# UBW32_MX460_v262.net
KiCad netlist of a schematic drawn in Altium Designer
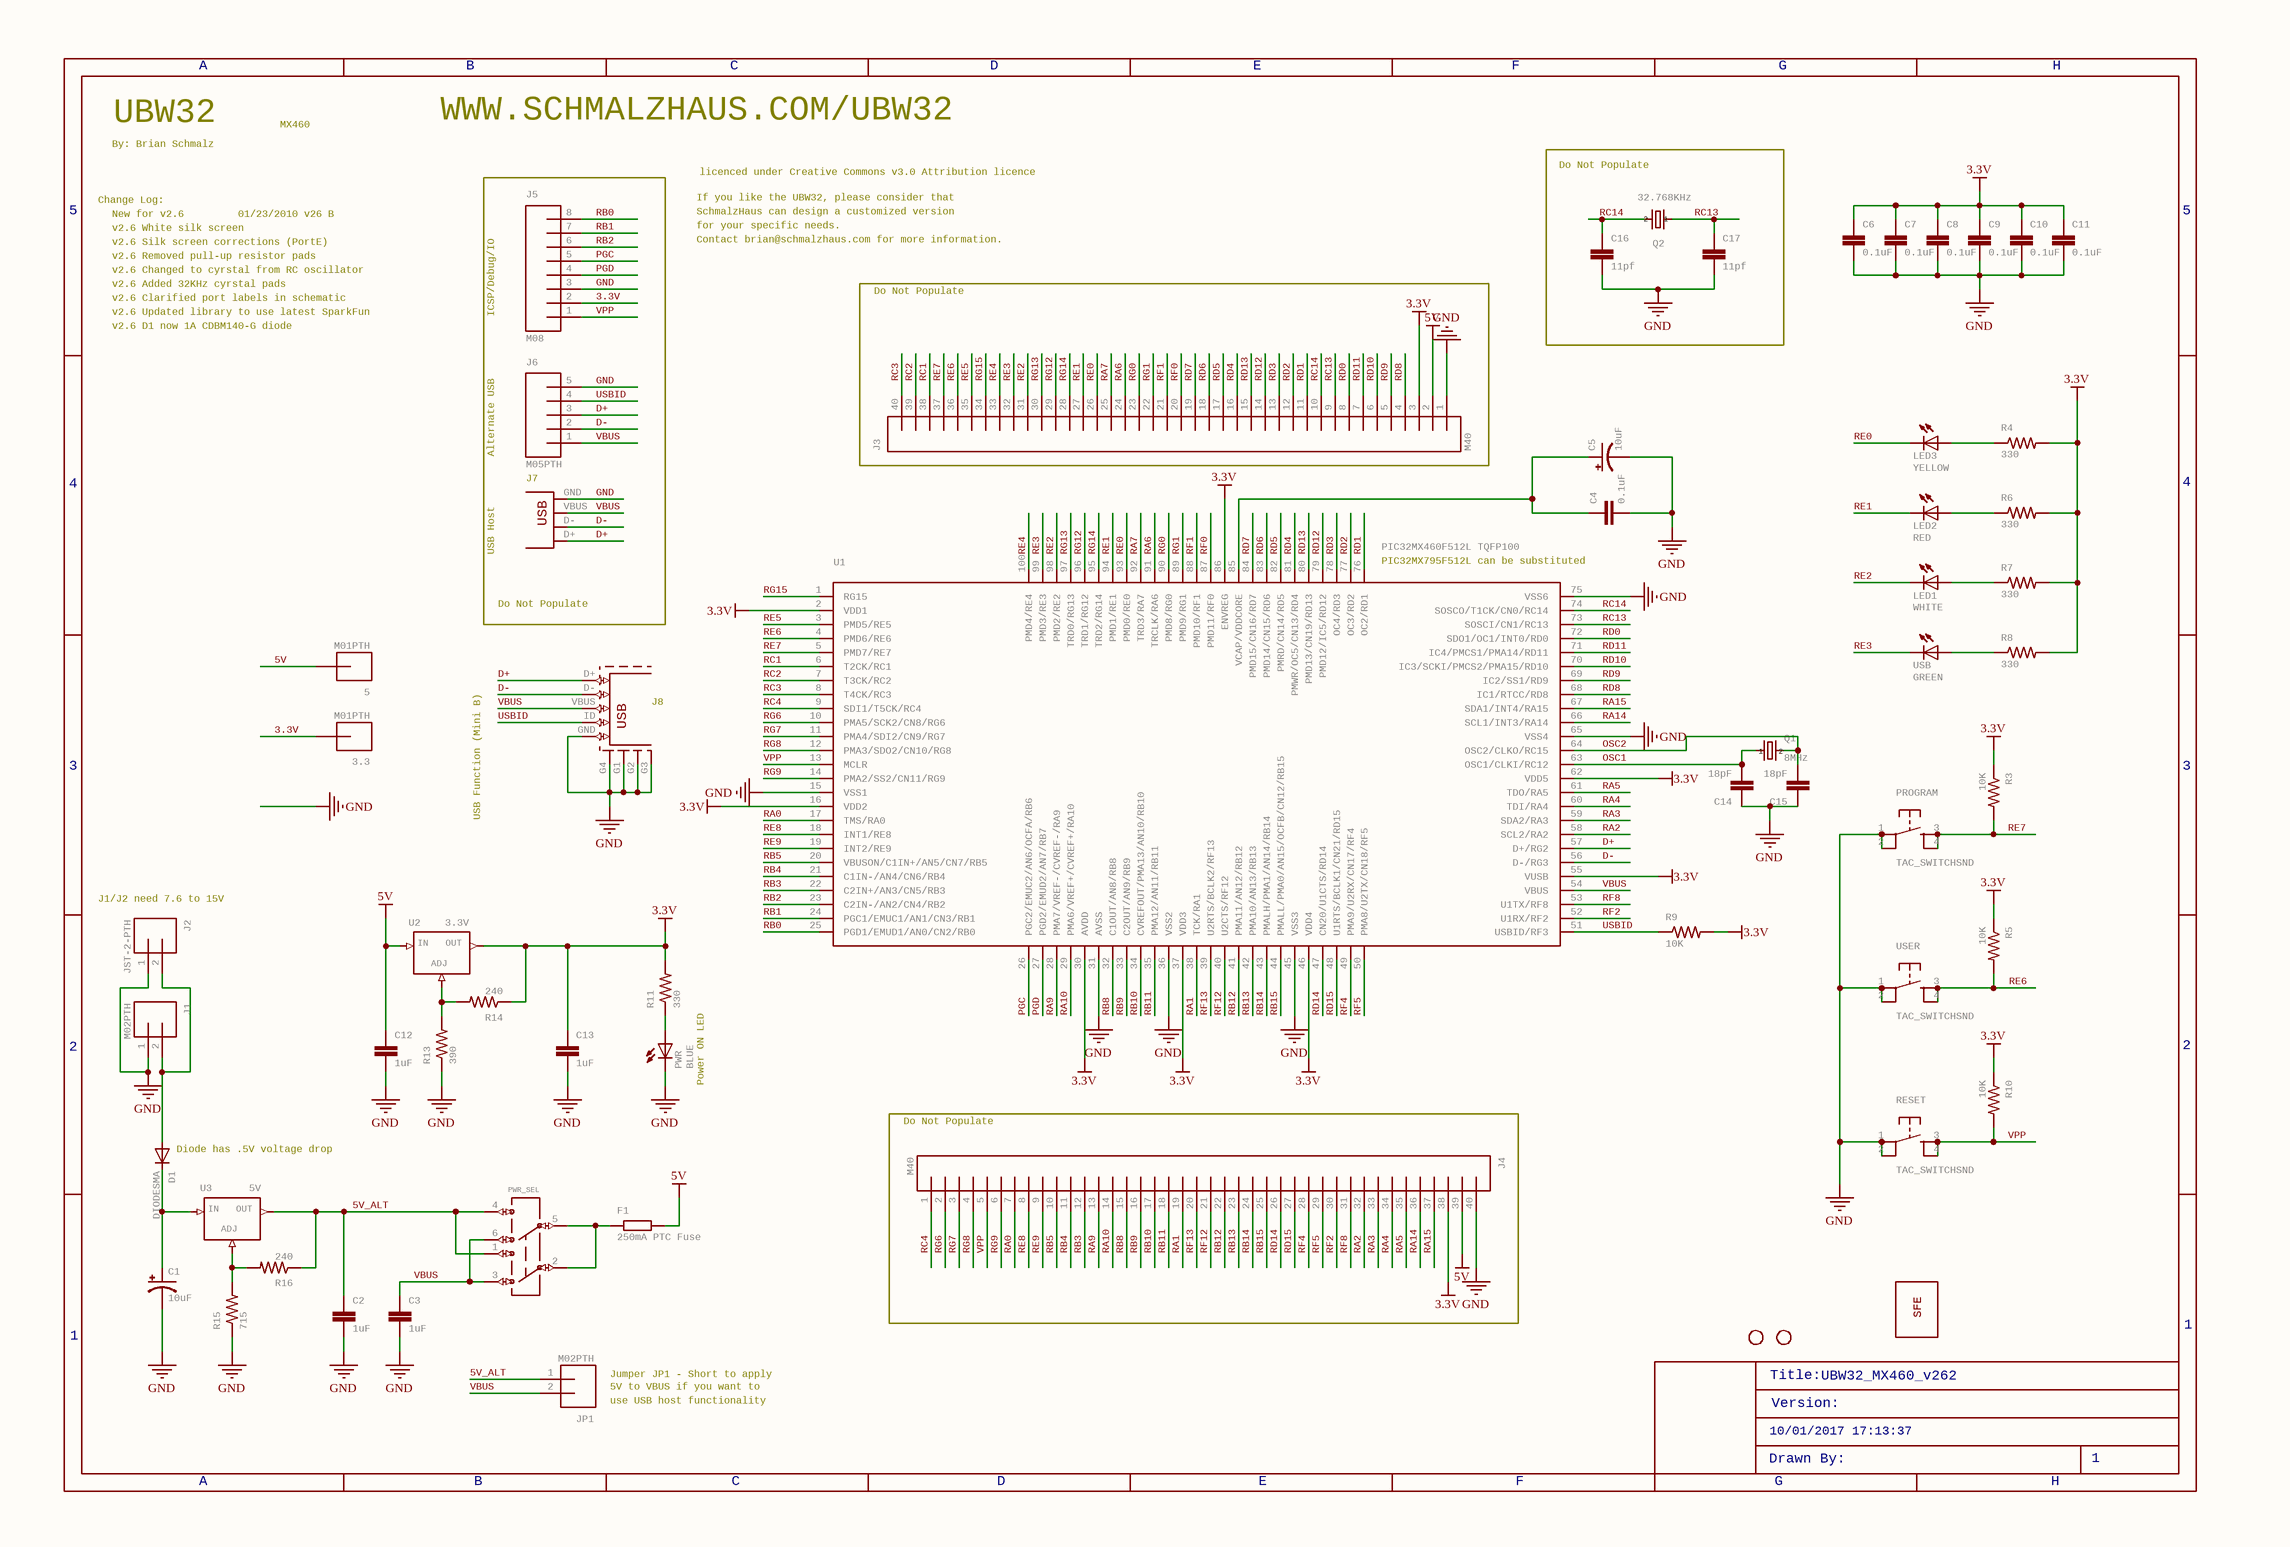
[diagram p0: UBW32_MX460_v262.SchDoc]

(export (version "E")
  (design (tool "Eeschema 10.0.6"))
  (components
    (comp (ref "3.3")
      (value "M01PTH")
      (footprint "1X01")
      (libsource (lib "SparkFun-12-01-09") (part "M01PTH"))
    )
    (comp (ref "5") (value "M01PTH") (footprint "1X01") (libsource (lib "SparkFun-12-01-09") (part "M01PTH")))
    (comp (ref "C1") (value "10uF") (footprint "EIA3528") (libsource (lib "") (part "CAP_POL3528_1")))
    (comp (ref "C2")
      (value "1uF")
      (footprint "0402-CAP")
      (description "CapacitorStandard 0603 ceramic capacitor, and 0.1\" leaded capacitor.")
      (libsource (lib "SparkFun") (part "CAP0402-CAP"))
    )
    (comp (ref "C3")
      (value "1uF")
      (footprint "0402-CAP")
      (description "CapacitorStandard 0603 ceramic capacitor, and 0.1\" leaded capacitor.")
      (libsource (lib "SparkFun") (part "CAP0402-CAP"))
    )
    (comp (ref "C4")
      (value "0.1uF")
      (footprint "0402-CAP")
      (description "CapacitorStandard 0603 ceramic capacitor, and 0.1\" leaded capacitor.")
      (libsource (lib "") (part "CAP0402-CAP_2"))
    )
    (comp (ref "C5")
      (value "10uF")
      (footprint "EIA3528")
      (libsource (lib "SparkFun02-20-08") (part "CAP_POL3528"))
    )
    (comp (ref "C6")
      (value "0.1uF")
      (footprint "0402-CAP")
      (description "CapacitorStandard 0603 ceramic capacitor, and 0.1\" leaded capacitor.")
      (libsource (lib "SparkFun") (part "CAP0402-CAP"))
    )
    (comp (ref "C7")
      (value "0.1uF")
      (footprint "0402-CAP")
      (description "CapacitorStandard 0603 ceramic capacitor, and 0.1\" leaded capacitor.")
      (libsource (lib "SparkFun") (part "CAP0402-CAP"))
    )
    (comp (ref "C8")
      (value "0.1uF")
      (footprint "0402-CAP")
      (description "CapacitorStandard 0603 ceramic capacitor, and 0.1\" leaded capacitor.")
      (libsource (lib "SparkFun") (part "CAP0402-CAP"))
    )
    (comp (ref "C9")
      (value "0.1uF")
      (footprint "0402-CAP")
      (description "CapacitorStandard 0603 ceramic capacitor, and 0.1\" leaded capacitor.")
      (libsource (lib "SparkFun") (part "CAP0402-CAP"))
    )
    (comp (ref "C10")
      (value "0.1uF")
      (footprint "C0402")
      (description "CapacitorStandard 0603 ceramic capacitor, and 0.1\" leaded capacitor.")
      (libsource (lib "SparkFun02-20-08") (part "CAP0402"))
    )
    (comp (ref "C11")
      (value "0.1uF")
      (footprint "0402-CAP")
      (description "CapacitorStandard 0603 ceramic capacitor, and 0.1\" leaded capacitor.")
      (libsource (lib "SparkFun") (part "CAP0402-CAP"))
    )
    (comp (ref "C12")
      (value "1uF")
      (footprint "C0402")
      (description "CapacitorStandard 0603 ceramic capacitor, and 0.1\" leaded capacitor.")
      (libsource (lib "SparkFun02-20-08") (part "CAP0402"))
    )
    (comp (ref "C13")
      (value "1uF")
      (footprint "C0402")
      (description "CapacitorStandard 0603 ceramic capacitor, and 0.1\" leaded capacitor.")
      (libsource (lib "SparkFun02-20-08") (part "CAP0402"))
    )
    (comp (ref "C14")
      (value "18pF")
      (footprint "0402-CAP")
      (description "CapacitorStandard 0603 ceramic capacitor, and 0.1\" leaded capacitor.")
      (libsource (lib "") (part "CAP0402-CAP_1"))
    )
    (comp (ref "C15")
      (value "18pF")
      (footprint "0402-CAP")
      (description "CapacitorStandard 0603 ceramic capacitor, and 0.1\" leaded capacitor.")
      (libsource (lib "") (part "CAP0402-CAP_1"))
    )
    (comp (ref "C16")
      (value "11pf")
      (footprint "0402-CAP")
      (description "CapacitorStandard 0603 ceramic capacitor, and 0.1\" leaded capacitor.")
      (libsource (lib "SparkFun") (part "CAP0402-CAP"))
    )
    (comp (ref "C17")
      (value "11pf")
      (footprint "0402-CAP")
      (description "CapacitorStandard 0603 ceramic capacitor, and 0.1\" leaded capacitor.")
      (libsource (lib "SparkFun") (part "CAP0402-CAP"))
    )
    (comp (ref "D1")
      (value "DIODESMA")
      (footprint "SMA-DIODE")
      (libsource (lib "SparkFun-12-01-09") (part "DIODESMA"))
    )
    (comp (ref "F1")
      (value "250mA PTC Fuse")
      (footprint "R1206")
      (description "RESISTOR, European symbol")
      (libsource (lib "resistor") (part "R-EU_R1206"))
    )
    (comp (ref "J1")
      (value "M02PTH")
      (footprint "1X02")
      (libsource (lib "SparkFun-12-01-09") (part "M02PTH"))
    )
    (comp (ref "J2")
      (value "JST-2-PTH")
      (footprint "S2B-PH")
      (libsource (lib "SparkFun") (part "M02-JST-2MM-SMT"))
    )
    (comp (ref "J3") (value "M40") (footprint "1X40") (libsource (lib "SchmalzHaus") (part "M40")))
    (comp (ref "J4") (value "M40") (footprint "1X40") (libsource (lib "SchmalzHaus") (part "M40")))
    (comp (ref "J5") (value "M08") (footprint "1X08") (libsource (lib "SchmalzHaus") (part "M08")))
    (comp (ref "J6")
      (value "M05PTH")
      (footprint "1X05")
      (libsource (lib "SparkFun-12-01-09") (part "M05PTH"))
    )
    (comp (ref "J7")
      (value "USB-A-S")
      (footprint "USB-A-S")
      (fields (field (name "USB") "USB"))
      (libsource (lib "SparkFun02-20-08") (part "USB-A-S"))
    )
    (comp (ref "J8")
      (value "~")
      (footprint "USB-MINIB")
      (fields (field (name "USB") "USB"))
      (libsource (lib "SparkFun02-20-08") (part "USB_5PIN"))
    )
    (comp (ref "JP1")
      (value "M02PTH")
      (footprint "1X02")
      (libsource (lib "SparkFun-12-01-09") (part "M02PTH"))
    )
    (comp (ref "LED1") (value "WHITE") (footprint "LED-0603") (libsource (lib "SparkFun") (part "LED0603")))
    (comp (ref "LED2") (value "RED") (footprint "LED-0603") (libsource (lib "SparkFun") (part "LED0603")))
    (comp (ref "LED3") (value "YELLOW") (footprint "LED-0603") (libsource (lib "SparkFun") (part "LED0603")))
    (comp (ref "PROGRAM")
      (value "TAC_SWITCHSND")
      (footprint "TACTILE_SWITCH_SMD")
      (libsource (lib "SparkFun02-20-08") (part "TAC_SWITCHSND"))
    )
    (comp (ref "PWR") (value "BLUE") (footprint "LED-0603") (libsource (lib "SparkFun") (part "LED0603")))
    (comp (ref "PWR_SEL")
      (value "AYZ0202")
      (footprint "AYZ0202")
      (libsource (lib "SparkFun02-20-08") (part "AYZ0202"))
    )
    (comp (ref "Q1")
      (value "8MHz")
      (footprint "CRYSTAL-SMD-5X3")
      (description "CrystalsVarious standard crystals. Proven footprints. Spark Fun Electronics SKU : COM-00534")
      (fields (field (name "1") "1") (field (name "2") "2"))
      (libsource (lib "SparkFun11_03_09") (part "CRYSTAL5X3"))
    )
    (comp (ref "Q2")
      (value "32.768KHz")
      (footprint "CRYSTAL-32KHZ-SMD")
      (description "CrystalsVarious standard crystals. Proven footprints. Spark Fun Electronics SKU : COM-00534")
      (fields (field (name "1") "1") (field (name "2") "2"))
      (libsource (lib "SchmalzHaus") (part "CRYSTAL32-SMD"))
    )
    (comp (ref "R3")
      (value "10K")
      (footprint "0402-RES")
      (libsource (lib "SparkFun") (part "RESISTOR0402-RES"))
    )
    (comp (ref "R4")
      (value "330")
      (footprint "0402-RES")
      (libsource (lib "SparkFun") (part "RESISTOR0402-RES"))
    )
    (comp (ref "R5")
      (value "10K")
      (footprint "0402-RES")
      (libsource (lib "SparkFun") (part "RESISTOR0402-RES"))
    )
    (comp (ref "R6")
      (value "330")
      (footprint "0402-RES")
      (libsource (lib "SparkFun") (part "RESISTOR0402-RES"))
    )
    (comp (ref "R7")
      (value "330")
      (footprint "0402-RES")
      (libsource (lib "SparkFun") (part "RESISTOR0402-RES"))
    )
    (comp (ref "R8")
      (value "330")
      (footprint "0402-RES")
      (libsource (lib "SparkFun") (part "RESISTOR0402-RES"))
    )
    (comp (ref "R9")
      (value "10K")
      (footprint "0402-RES")
      (libsource (lib "SparkFun") (part "RESISTOR0402-RES"))
    )
    (comp (ref "R10")
      (value "10K")
      (footprint "0402-RES")
      (libsource (lib "SparkFun") (part "RESISTOR0402-RES"))
    )
    (comp (ref "R11")
      (value "330")
      (footprint "0402-RES")
      (libsource (lib "SparkFun") (part "RESISTOR0402-RES"))
    )
    (comp (ref "R13")
      (value "390")
      (footprint "0402-RES")
      (libsource (lib "SparkFun") (part "RESISTOR0402-RES"))
    )
    (comp (ref "R14")
      (value "240")
      (footprint "0402-RES")
      (libsource (lib "SparkFun") (part "RESISTOR0402-RES"))
    )
    (comp (ref "R15")
      (value "715")
      (footprint "0402-RES")
      (libsource (lib "SparkFun") (part "RESISTOR0402-RES"))
    )
    (comp (ref "R16")
      (value "240")
      (footprint "0402-RES")
      (libsource (lib "SparkFun") (part "RESISTOR0402-RES"))
    )
    (comp (ref "RESET")
      (value "TAC_SWITCHSND")
      (footprint "TACTILE_SWITCH_SMD")
      (libsource (lib "SparkFun02-20-08") (part "TAC_SWITCHSND"))
    )
    (comp (ref "U$4")
      (value "LOGO-SFENEW")
      (footprint "SFE-NEW-WEBLOGO")
      (description "Spark Fun Electronics PCB LogoThis is the standard Spark Fun Electronics PCB logo.")
      (fields (field (name "SFE") "SFE"))
      (libsource (lib "SparkFun02-20-08") (part "LOGO-SFENEW"))
    )
    (comp (ref "U$6")
      (value "STAND-OFF")
      (footprint "STAND-OFF")
      (libsource (lib "SparkFun02-20-08") (part "STAND-OFF"))
    )
    (comp (ref "U$7")
      (value "STAND-OFF")
      (footprint "STAND-OFF")
      (libsource (lib "SparkFun02-20-08") (part "STAND-OFF"))
    )
    (comp (ref "U1")
      (value "PIC32MX460F512L TQFP100")
      (footprint "TQFP100")
      (libsource (lib "SchmalzHaus") (part "PIC32MX4XXLTQFP100"))
    )
    (comp (ref "U2")
      (value "3.3V")
      (footprint "SOT223")
      (fields (field (name "ADJ") "ADJ") (field (name "IN") "IN") (field (name "OUT") "OUT"))
      (libsource (lib "SparkFun") (part "V_REG_317SMD"))
    )
    (comp (ref "U3")
      (value "5V")
      (footprint "SOT223")
      (fields (field (name "ADJ") "ADJ") (field (name "IN") "IN") (field (name "OUT") "OUT"))
      (libsource (lib "SparkFun") (part "V_REG_317SMD"))
    )
    (comp (ref "USB") (value "GREEN") (footprint "LED-0603") (libsource (lib "SparkFun") (part "LED0603")))
    (comp (ref "USER")
      (value "TAC_SWITCHSND")
      (footprint "TACTILE_SWITCH_SMD")
      (libsource (lib "SparkFun02-20-08") (part "TAC_SWITCHSND"))
    )
  )
  (nets
    (net (code "1") (name "/5V_ALT") (class "Default")
      (node (ref "C2") (pin "1") (pinfunction "1_1") (pintype "passive"))
      (node (ref "JP1") (pin "1") (pinfunction "1_1") (pintype "passive"))
      (node (ref "PWR_SEL") (pin "1") (pinfunction "3_1") (pintype "bidirectional"))
      (node (ref "PWR_SEL") (pin "4") (pinfunction "6_4") (pintype "bidirectional"))
      (node (ref "R16") (pin "1") (pinfunction "1_1") (pintype "passive"))
      (node (ref "U3") (pin "2") (pinfunction "OUT_2") (pintype "output"))
    )
    (net (code "2") (name "/D+") (class "Default")
      (node (ref "J6") (pin "3") (pinfunction "3_3") (pintype "passive"))
      (node (ref "J7") (pin "D+") (pinfunction "D+_D+") (pintype "bidirectional"))
      (node (ref "J8") (pin "D+") (pinfunction "D+_D+") (pintype "bidirectional"))
      (node (ref "U1") (pin "57") (pinfunction "D+/RG2_57") (pintype "bidirectional"))
    )
    (net (code "3") (name "/D-") (class "Default")
      (node (ref "J6") (pin "2") (pinfunction "2_2") (pintype "passive"))
      (node (ref "J7") (pin "D-") (pinfunction "D-_D-") (pintype "bidirectional"))
      (node (ref "J8") (pin "D-") (pinfunction "D-_D-") (pintype "bidirectional"))
      (node (ref "U1") (pin "56") (pinfunction "D-/RG3_56") (pintype "bidirectional"))
    )
    (net (code "4") (name "/OSC1") (class "Default")
      (node (ref "C14") (pin "2") (pinfunction "2_2") (pintype "passive"))
      (node (ref "Q1") (pin "1") (pinfunction "1_1") (pintype "passive"))
      (node (ref "U1") (pin "63") (pinfunction "OSC1/CLKI/RC12_63") (pintype "bidirectional"))
    )
    (net (code "5") (name "/OSC2") (class "Default")
      (node (ref "C15") (pin "2") (pinfunction "2_2") (pintype "passive"))
      (node (ref "Q1") (pin "3") (pinfunction "2_3") (pintype "passive"))
      (node (ref "U1") (pin "64") (pinfunction "OSC2/CLKO/RC15_64") (pintype "bidirectional"))
    )
    (net (code "6") (name "/PGC") (class "Default")
      (node (ref "J5") (pin "5") (pinfunction "5_5") (pintype "passive"))
      (node (ref "U1") (pin "26") (pinfunction "PGC2/EMUC2/AN6/OCFA/RB6_26") (pintype "bidirectional"))
    )
    (net (code "7") (name "/PGD") (class "Default")
      (node (ref "J5") (pin "4") (pinfunction "4_4") (pintype "passive"))
      (node (ref "U1") (pin "27") (pinfunction "PGD2/EMUD2/AN7/RB7_27") (pintype "bidirectional"))
    )
    (net (code "8") (name "/RA0") (class "Default")
      (node (ref "J4") (pin "7") (pinfunction "7_7") (pintype "passive"))
      (node (ref "U1") (pin "17") (pinfunction "TMS/RA0_17") (pintype "bidirectional"))
    )
    (net (code "9") (name "/RA1") (class "Default")
      (node (ref "J4") (pin "19") (pinfunction "19_19") (pintype "passive"))
      (node (ref "U1") (pin "38") (pinfunction "TCK/RA1_38") (pintype "bidirectional"))
    )
    (net (code "10") (name "/RA2") (class "Default")
      (node (ref "J4") (pin "32") (pinfunction "32_32") (pintype "passive"))
      (node (ref "U1") (pin "58") (pinfunction "SCL2/RA2_58") (pintype "bidirectional"))
    )
    (net (code "11") (name "/RA3") (class "Default")
      (node (ref "J4") (pin "33") (pinfunction "33_33") (pintype "passive"))
      (node (ref "U1") (pin "59") (pinfunction "SDA2/RA3_59") (pintype "bidirectional"))
    )
    (net (code "12") (name "/RA4") (class "Default")
      (node (ref "J4") (pin "34") (pinfunction "34_34") (pintype "passive"))
      (node (ref "U1") (pin "60") (pinfunction "TDI/RA4_60") (pintype "bidirectional"))
    )
    (net (code "13") (name "/RA5") (class "Default")
      (node (ref "J4") (pin "35") (pinfunction "35_35") (pintype "passive"))
      (node (ref "U1") (pin "61") (pinfunction "TDO/RA5_61") (pintype "bidirectional"))
    )
    (net (code "14") (name "/RA6") (class "Default")
      (node (ref "J3") (pin "24") (pinfunction "24_24") (pintype "passive"))
      (node (ref "U1") (pin "91") (pinfunction "TRCLK/RA6_91") (pintype "bidirectional"))
    )
    (net (code "15") (name "/RA7") (class "Default")
      (node (ref "J3") (pin "25") (pinfunction "25_25") (pintype "passive"))
      (node (ref "U1") (pin "92") (pinfunction "TRD3/RA7_92") (pintype "bidirectional"))
    )
    (net (code "16") (name "/RA9") (class "Default")
      (node (ref "J4") (pin "13") (pinfunction "13_13") (pintype "passive"))
      (node (ref "U1") (pin "28") (pinfunction "PMA7/VREF-/CVREF-/RA9_28") (pintype "bidirectional"))
    )
    (net (code "17") (name "/RA10") (class "Default")
      (node (ref "J4") (pin "14") (pinfunction "14_14") (pintype "passive"))
      (node (ref "U1") (pin "29") (pinfunction "PMA6/VREF+/CVREF+/RA10_29") (pintype "bidirectional"))
    )
    (net (code "18") (name "/RA14") (class "Default")
      (node (ref "J4") (pin "36") (pinfunction "36_36") (pintype "passive"))
      (node (ref "U1") (pin "66") (pinfunction "SCL1/INT3/RA14_66") (pintype "bidirectional"))
    )
    (net (code "19") (name "/RA15") (class "Default")
      (node (ref "J4") (pin "37") (pinfunction "37_37") (pintype "passive"))
      (node (ref "U1") (pin "67") (pinfunction "SDA1/INT4/RA15_67") (pintype "bidirectional"))
    )
    (net (code "20") (name "/RB0") (class "Default")
      (node (ref "J5") (pin "8") (pinfunction "8_8") (pintype "passive"))
      (node (ref "U1") (pin "25") (pinfunction "PGD1/EMUD1/AN0/CN2/RB0_25") (pintype "bidirectional"))
    )
    (net (code "21") (name "/RB1") (class "Default")
      (node (ref "J5") (pin "7") (pinfunction "7_7") (pintype "passive"))
      (node (ref "U1") (pin "24") (pinfunction "PGC1/EMUC1/AN1/CN3/RB1_24") (pintype "bidirectional"))
    )
    (net (code "22") (name "/RB2") (class "Default")
      (node (ref "J5") (pin "6") (pinfunction "6_6") (pintype "passive"))
      (node (ref "U1") (pin "23") (pinfunction "C2IN-/AN2/CN4/RB2_23") (pintype "bidirectional"))
    )
    (net (code "23") (name "/RB3") (class "Default")
      (node (ref "J4") (pin "12") (pinfunction "12_12") (pintype "passive"))
      (node (ref "U1") (pin "22") (pinfunction "C2IN+/AN3/CN5/RB3_22") (pintype "bidirectional"))
    )
    (net (code "24") (name "/RB4") (class "Default")
      (node (ref "J4") (pin "11") (pinfunction "11_11") (pintype "passive"))
      (node (ref "U1") (pin "21") (pinfunction "C1IN-/AN4/CN6/RB4_21") (pintype "bidirectional"))
    )
    (net (code "25") (name "/RB5") (class "Default")
      (node (ref "J4") (pin "10") (pinfunction "10_10") (pintype "passive"))
      (node (ref "U1") (pin "20") (pinfunction "VBUSON/C1IN+/AN5/CN7/RB5_20") (pintype "bidirectional"))
    )
    (net (code "26") (name "/RB8") (class "Default")
      (node (ref "J4") (pin "15") (pinfunction "15_15") (pintype "passive"))
      (node (ref "U1") (pin "32") (pinfunction "C1OUT/AN8/RB8_32") (pintype "bidirectional"))
    )
    (net (code "27") (name "/RB9") (class "Default")
      (node (ref "J4") (pin "16") (pinfunction "16_16") (pintype "passive"))
      (node (ref "U1") (pin "33") (pinfunction "C2OUT/AN9/RB9_33") (pintype "bidirectional"))
    )
    (net (code "28") (name "/RB10") (class "Default")
      (node (ref "J4") (pin "17") (pinfunction "17_17") (pintype "passive"))
      (node (ref "U1") (pin "34") (pinfunction "CVREFOUT/PMA13/AN10/RB10_34") (pintype "bidirectional"))
    )
    (net (code "29") (name "/RB11") (class "Default")
      (node (ref "J4") (pin "18") (pinfunction "18_18") (pintype "passive"))
      (node (ref "U1") (pin "35") (pinfunction "PMA12/AN11/RB11_35") (pintype "bidirectional"))
    )
    (net (code "30") (name "/RB12") (class "Default")
      (node (ref "J4") (pin "22") (pinfunction "22_22") (pintype "passive"))
      (node (ref "U1") (pin "41") (pinfunction "PMA11/AN12/RB12_41") (pintype "bidirectional"))
    )
    (net (code "31") (name "/RB13") (class "Default")
      (node (ref "J4") (pin "23") (pinfunction "23_23") (pintype "passive"))
      (node (ref "U1") (pin "42") (pinfunction "PMA10/AN13/RB13_42") (pintype "bidirectional"))
    )
    (net (code "32") (name "/RB14") (class "Default")
      (node (ref "J4") (pin "24") (pinfunction "24_24") (pintype "passive"))
      (node (ref "U1") (pin "43") (pinfunction "PMALH/PMA1/AN14/RB14_43") (pintype "bidirectional"))
    )
    (net (code "33") (name "/RB15") (class "Default")
      (node (ref "J4") (pin "25") (pinfunction "25_25") (pintype "passive"))
      (node (ref "U1") (pin "44") (pinfunction "PMALL/PMA0/AN15/OCFB/CN12/RB15_44") (pintype "bidirectional"))
    )
    (net (code "34") (name "/RC1") (class "Default")
      (node (ref "J3") (pin "38") (pinfunction "38_38") (pintype "passive"))
      (node (ref "U1") (pin "6") (pinfunction "T2CK/RC1_6") (pintype "bidirectional"))
    )
    (net (code "35") (name "/RC2") (class "Default")
      (node (ref "J3") (pin "39") (pinfunction "39_39") (pintype "passive"))
      (node (ref "U1") (pin "7") (pinfunction "T3CK/RC2_7") (pintype "bidirectional"))
    )
    (net (code "36") (name "/RC3") (class "Default")
      (node (ref "J3") (pin "40") (pinfunction "40_40") (pintype "passive"))
      (node (ref "U1") (pin "8") (pinfunction "T4CK/RC3_8") (pintype "bidirectional"))
    )
    (net (code "37") (name "/RC4") (class "Default")
      (node (ref "J4") (pin "1") (pinfunction "1_1") (pintype "passive"))
      (node (ref "U1") (pin "9") (pinfunction "SDI1/T5CK/RC4_9") (pintype "bidirectional"))
    )
    (net (code "38") (name "/RC13") (class "Default")
      (node (ref "C17") (pin "1") (pinfunction "1_1") (pintype "passive"))
      (node (ref "J3") (pin "9") (pinfunction "9_9") (pintype "passive"))
      (node (ref "Q2") (pin "X1") (pinfunction "1_X1") (pintype "passive"))
      (node (ref "U1") (pin "73") (pinfunction "SOSCI/CN1/RC13_73") (pintype "bidirectional"))
    )
    (net (code "39") (name "/RC14") (class "Default")
      (node (ref "C16") (pin "1") (pinfunction "1_1") (pintype "passive"))
      (node (ref "J3") (pin "10") (pinfunction "10_10") (pintype "passive"))
      (node (ref "Q2") (pin "X2") (pinfunction "2_X2") (pintype "passive"))
      (node (ref "U1") (pin "74") (pinfunction "SOSCO/T1CK/CN0/RC14_74") (pintype "bidirectional"))
    )
    (net (code "40") (name "/RD0") (class "Default")
      (node (ref "J3") (pin "8") (pinfunction "8_8") (pintype "passive"))
      (node (ref "U1") (pin "72") (pinfunction "SDO1/OC1/INT0/RD0_72") (pintype "bidirectional"))
    )
    (net (code "41") (name "/RD1") (class "Default")
      (node (ref "J3") (pin "11") (pinfunction "11_11") (pintype "passive"))
      (node (ref "U1") (pin "76") (pinfunction "OC2/RD1_76") (pintype "bidirectional"))
    )
    (net (code "42") (name "/RD2") (class "Default")
      (node (ref "J3") (pin "12") (pinfunction "12_12") (pintype "passive"))
      (node (ref "U1") (pin "77") (pinfunction "OC3/RD2_77") (pintype "bidirectional"))
    )
    (net (code "43") (name "/RD3") (class "Default")
      (node (ref "J3") (pin "13") (pinfunction "13_13") (pintype "passive"))
      (node (ref "U1") (pin "78") (pinfunction "OC4/RD3_78") (pintype "bidirectional"))
    )
    (net (code "44") (name "/RD4") (class "Default")
      (node (ref "J3") (pin "16") (pinfunction "16_16") (pintype "passive"))
      (node (ref "U1") (pin "81") (pinfunction "PMWR/OC5/CN13/RD4_81") (pintype "bidirectional"))
    )
    (net (code "45") (name "/RD5") (class "Default")
      (node (ref "J3") (pin "17") (pinfunction "17_17") (pintype "passive"))
      (node (ref "U1") (pin "82") (pinfunction "PMRD/CN14/RD5_82") (pintype "bidirectional"))
    )
    (net (code "46") (name "/RD6") (class "Default")
      (node (ref "J3") (pin "18") (pinfunction "18_18") (pintype "passive"))
      (node (ref "U1") (pin "83") (pinfunction "PMD14/CN15/RD6_83") (pintype "bidirectional"))
    )
    (net (code "47") (name "/RD7") (class "Default")
      (node (ref "J3") (pin "19") (pinfunction "19_19") (pintype "passive"))
      (node (ref "U1") (pin "84") (pinfunction "PMD15/CN16/RD7_84") (pintype "bidirectional"))
    )
    (net (code "48") (name "/RD8") (class "Default")
      (node (ref "J3") (pin "4") (pinfunction "4_4") (pintype "passive"))
      (node (ref "U1") (pin "68") (pinfunction "IC1/RTCC/RD8_68") (pintype "bidirectional"))
    )
    (net (code "49") (name "/RD9") (class "Default")
      (node (ref "J3") (pin "5") (pinfunction "5_5") (pintype "passive"))
      (node (ref "U1") (pin "69") (pinfunction "IC2/SS1/RD9_69") (pintype "bidirectional"))
    )
    (net (code "50") (name "/RD10") (class "Default")
      (node (ref "J3") (pin "6") (pinfunction "6_6") (pintype "passive"))
      (node (ref "U1") (pin "70") (pinfunction "IC3/SCKI/PMCS2/PMA15/RD10_70") (pintype "bidirectional"))
    )
    (net (code "51") (name "/RD11") (class "Default")
      (node (ref "J3") (pin "7") (pinfunction "7_7") (pintype "passive"))
      (node (ref "U1") (pin "71") (pinfunction "IC4/PMCS1/PMA14/RD11_71") (pintype "bidirectional"))
    )
    (net (code "52") (name "/RD12") (class "Default")
      (node (ref "J3") (pin "14") (pinfunction "14_14") (pintype "passive"))
      (node (ref "U1") (pin "79") (pinfunction "PMD12/IC5/RD12_79") (pintype "bidirectional"))
    )
    (net (code "53") (name "/RD13") (class "Default")
      (node (ref "J3") (pin "15") (pinfunction "15_15") (pintype "passive"))
      (node (ref "U1") (pin "80") (pinfunction "PMD13/CN19/RD13_80") (pintype "bidirectional"))
    )
    (net (code "54") (name "/RD14") (class "Default")
      (node (ref "J4") (pin "26") (pinfunction "26_26") (pintype "passive"))
      (node (ref "U1") (pin "47") (pinfunction "CN20/U1CTS/RD14_47") (pintype "bidirectional"))
    )
    (net (code "55") (name "/RD15") (class "Default")
      (node (ref "J4") (pin "27") (pinfunction "27_27") (pintype "passive"))
      (node (ref "U1") (pin "48") (pinfunction "U1RTS/BCLK1/CN21/RD15_48") (pintype "bidirectional"))
    )
    (net (code "56") (name "/RE0") (class "Default")
      (node (ref "J3") (pin "26") (pinfunction "26_26") (pintype "passive"))
      (node (ref "LED3") (pin "C") (pinfunction "C_C") (pintype "passive"))
      (node (ref "U1") (pin "93") (pinfunction "PMD0/RE0_93") (pintype "bidirectional"))
    )
    (net (code "57") (name "/RE1") (class "Default")
      (node (ref "J3") (pin "27") (pinfunction "27_27") (pintype "passive"))
      (node (ref "LED2") (pin "C") (pinfunction "C_C") (pintype "passive"))
      (node (ref "U1") (pin "94") (pinfunction "PMD1/RE1_94") (pintype "bidirectional"))
    )
    (net (code "58") (name "/RE2") (class "Default")
      (node (ref "J3") (pin "31") (pinfunction "31_31") (pintype "passive"))
      (node (ref "LED1") (pin "C") (pinfunction "C_C") (pintype "passive"))
      (node (ref "U1") (pin "98") (pinfunction "PMD2/RE2_98") (pintype "bidirectional"))
    )
    (net (code "59") (name "/RE3") (class "Default")
      (node (ref "J3") (pin "32") (pinfunction "32_32") (pintype "passive"))
      (node (ref "U1") (pin "99") (pinfunction "PMD3/RE3_99") (pintype "bidirectional"))
      (node (ref "USB") (pin "C") (pinfunction "C_C") (pintype "passive"))
    )
    (net (code "60") (name "/RE4") (class "Default")
      (node (ref "J3") (pin "33") (pinfunction "33_33") (pintype "passive"))
      (node (ref "U1") (pin "100") (pinfunction "PMD4/RE4_100") (pintype "bidirectional"))
    )
    (net (code "61") (name "/RE5") (class "Default")
      (node (ref "J3") (pin "35") (pinfunction "35_35") (pintype "passive"))
      (node (ref "U1") (pin "3") (pinfunction "PMD5/RE5_3") (pintype "bidirectional"))
    )
    (net (code "62") (name "/RE6") (class "Default")
      (node (ref "J3") (pin "36") (pinfunction "36_36") (pintype "passive"))
      (node (ref "R5") (pin "2") (pinfunction "2_2") (pintype "passive"))
      (node (ref "U1") (pin "4") (pinfunction "PMD6/RE6_4") (pintype "bidirectional"))
      (node (ref "USER") (pin "3") (pinfunction "3_3") (pintype "passive"))
      (node (ref "USER") (pin "4") (pinfunction "4_4") (pintype "passive"))
    )
    (net (code "63") (name "/RE7") (class "Default")
      (node (ref "J3") (pin "37") (pinfunction "37_37") (pintype "passive"))
      (node (ref "PROGRAM") (pin "3") (pinfunction "3_3") (pintype "passive"))
      (node (ref "PROGRAM") (pin "4") (pinfunction "4_4") (pintype "passive"))
      (node (ref "R3") (pin "2") (pinfunction "2_2") (pintype "passive"))
      (node (ref "U1") (pin "5") (pinfunction "PMD7/RE7_5") (pintype "bidirectional"))
    )
    (net (code "64") (name "/RE8") (class "Default")
      (node (ref "J4") (pin "8") (pinfunction "8_8") (pintype "passive"))
      (node (ref "U1") (pin "18") (pinfunction "INT1/RE8_18") (pintype "bidirectional"))
    )
    (net (code "65") (name "/RE9") (class "Default")
      (node (ref "J4") (pin "9") (pinfunction "9_9") (pintype "passive"))
      (node (ref "U1") (pin "19") (pinfunction "INT2/RE9_19") (pintype "bidirectional"))
    )
    (net (code "66") (name "/RF0") (class "Default")
      (node (ref "J3") (pin "20") (pinfunction "20_20") (pintype "passive"))
      (node (ref "U1") (pin "87") (pinfunction "PMD11/RF0_87") (pintype "bidirectional"))
    )
    (net (code "67") (name "/RF1") (class "Default")
      (node (ref "J3") (pin "21") (pinfunction "21_21") (pintype "passive"))
      (node (ref "U1") (pin "88") (pinfunction "PMD10/RF1_88") (pintype "bidirectional"))
    )
    (net (code "68") (name "/RF2") (class "Default")
      (node (ref "J4") (pin "30") (pinfunction "30_30") (pintype "passive"))
      (node (ref "U1") (pin "52") (pinfunction "U1RX/RF2_52") (pintype "bidirectional"))
    )
    (net (code "69") (name "/RF4") (class "Default")
      (node (ref "J4") (pin "28") (pinfunction "28_28") (pintype "passive"))
      (node (ref "U1") (pin "49") (pinfunction "PMA9/U2RX/CN17/RF4_49") (pintype "bidirectional"))
    )
    (net (code "70") (name "/RF5") (class "Default")
      (node (ref "J4") (pin "29") (pinfunction "29_29") (pintype "passive"))
      (node (ref "U1") (pin "50") (pinfunction "PMA8/U2TX/CN18/RF5_50") (pintype "bidirectional"))
    )
    (net (code "71") (name "/RF8") (class "Default")
      (node (ref "J4") (pin "31") (pinfunction "31_31") (pintype "passive"))
      (node (ref "U1") (pin "53") (pinfunction "U1TX/RF8_53") (pintype "bidirectional"))
    )
    (net (code "72") (name "/RF12") (class "Default")
      (node (ref "J4") (pin "21") (pinfunction "21_21") (pintype "passive"))
      (node (ref "U1") (pin "40") (pinfunction "U2CTS/RF12_40") (pintype "bidirectional"))
    )
    (net (code "73") (name "/RF13") (class "Default")
      (node (ref "J4") (pin "20") (pinfunction "20_20") (pintype "passive"))
      (node (ref "U1") (pin "39") (pinfunction "U2RTS/BCLK2/RF13_39") (pintype "bidirectional"))
    )
    (net (code "74") (name "/RG0") (class "Default")
      (node (ref "J3") (pin "23") (pinfunction "23_23") (pintype "passive"))
      (node (ref "U1") (pin "90") (pinfunction "PMD8/RG0_90") (pintype "bidirectional"))
    )
    (net (code "75") (name "/RG1") (class "Default")
      (node (ref "J3") (pin "22") (pinfunction "22_22") (pintype "passive"))
      (node (ref "U1") (pin "89") (pinfunction "PMD9/RG1_89") (pintype "bidirectional"))
    )
    (net (code "76") (name "/RG6") (class "Default")
      (node (ref "J4") (pin "2") (pinfunction "2_2") (pintype "passive"))
      (node (ref "U1") (pin "10") (pinfunction "PMA5/SCK2/CN8/RG6_10") (pintype "bidirectional"))
    )
    (net (code "77") (name "/RG7") (class "Default")
      (node (ref "J4") (pin "3") (pinfunction "3_3") (pintype "passive"))
      (node (ref "U1") (pin "11") (pinfunction "PMA4/SDI2/CN9/RG7_11") (pintype "bidirectional"))
    )
    (net (code "78") (name "/RG8") (class "Default")
      (node (ref "J4") (pin "4") (pinfunction "4_4") (pintype "passive"))
      (node (ref "U1") (pin "12") (pinfunction "PMA3/SDO2/CN10/RG8_12") (pintype "bidirectional"))
    )
    (net (code "79") (name "/RG9") (class "Default")
      (node (ref "J4") (pin "6") (pinfunction "6_6") (pintype "passive"))
      (node (ref "U1") (pin "14") (pinfunction "PMA2/SS2/CN11/RG9_14") (pintype "bidirectional"))
    )
    (net (code "80") (name "/RG12") (class "Default")
      (node (ref "J3") (pin "29") (pinfunction "29_29") (pintype "passive"))
      (node (ref "U1") (pin "96") (pinfunction "TRD1/RG12_96") (pintype "bidirectional"))
    )
    (net (code "81") (name "/RG13") (class "Default")
      (node (ref "J3") (pin "30") (pinfunction "30_30") (pintype "passive"))
      (node (ref "U1") (pin "97") (pinfunction "TRD0/RG13_97") (pintype "bidirectional"))
    )
    (net (code "82") (name "/RG14") (class "Default")
      (node (ref "J3") (pin "28") (pinfunction "28_28") (pintype "passive"))
      (node (ref "U1") (pin "95") (pinfunction "TRD2/RG14_95") (pintype "bidirectional"))
    )
    (net (code "83") (name "/RG15") (class "Default")
      (node (ref "J3") (pin "34") (pinfunction "34_34") (pintype "passive"))
      (node (ref "U1") (pin "1") (pinfunction "RG15_1") (pintype "bidirectional"))
    )
    (net (code "84") (name "/USBID") (class "Default")
      (node (ref "J6") (pin "4") (pinfunction "4_4") (pintype "passive"))
      (node (ref "J8") (pin "ID") (pinfunction "USB_ID_ID") (pintype "bidirectional"))
      (node (ref "R9") (pin "1") (pinfunction "1_1") (pintype "passive"))
      (node (ref "U1") (pin "51") (pinfunction "USBID/RF3_51") (pintype "bidirectional"))
    )
    (net (code "85") (name "/VBUS") (class "Default")
      (node (ref "C3") (pin "1") (pinfunction "1_1") (pintype "passive"))
      (node (ref "J6") (pin "1") (pinfunction "1_1") (pintype "passive"))
      (node (ref "J7") (pin "VBUS") (pinfunction "VBUS_VBUS") (pintype "bidirectional"))
      (node (ref "J8") (pin "VBUS") (pinfunction "VBUS_VBUS") (pintype "bidirectional"))
      (node (ref "JP1") (pin "2") (pinfunction "2_2") (pintype "passive"))
      (node (ref "PWR_SEL") (pin "3") (pinfunction "1_3") (pintype "bidirectional"))
      (node (ref "PWR_SEL") (pin "6") (pinfunction "4_6") (pintype "bidirectional"))
      (node (ref "U1") (pin "54") (pinfunction "VBUS_54") (pintype "bidirectional"))
    )
    (net (code "86") (name "/VPP") (class "Default")
      (node (ref "J4") (pin "5") (pinfunction "5_5") (pintype "passive"))
      (node (ref "J5") (pin "1") (pinfunction "1_1") (pintype "passive"))
      (node (ref "R10") (pin "2") (pinfunction "2_2") (pintype "passive"))
      (node (ref "RESET") (pin "3") (pinfunction "3_3") (pintype "passive"))
      (node (ref "RESET") (pin "4") (pinfunction "4_4") (pintype "passive"))
      (node (ref "U1") (pin "13") (pinfunction "MCLR_13") (pintype "bidirectional"))
    )
    (net (code "87") (name "3.3V") (class "Default")
      (node (ref "3.3") (pin "1") (pinfunction "1_1") (pintype "passive"))
      (node (ref "C10") (pin "1") (pinfunction "1_1") (pintype "passive"))
      (node (ref "C11") (pin "1") (pinfunction "1_1") (pintype "passive"))
      (node (ref "C13") (pin "1") (pinfunction "1_1") (pintype "passive"))
      (node (ref "C6") (pin "1") (pinfunction "1_1") (pintype "passive"))
      (node (ref "C7") (pin "1") (pinfunction "1_1") (pintype "passive"))
      (node (ref "C8") (pin "1") (pinfunction "1_1") (pintype "passive"))
      (node (ref "C9") (pin "1") (pinfunction "1_1") (pintype "passive"))
      (node (ref "J3") (pin "3") (pinfunction "3_3") (pintype "passive"))
      (node (ref "J4") (pin "38") (pinfunction "38_38") (pintype "passive"))
      (node (ref "J5") (pin "2") (pinfunction "2_2") (pintype "passive"))
      (node (ref "R10") (pin "1") (pinfunction "1_1") (pintype "passive"))
      (node (ref "R11") (pin "2") (pinfunction "2_2") (pintype "passive"))
      (node (ref "R14") (pin "1") (pinfunction "1_1") (pintype "passive"))
      (node (ref "R3") (pin "1") (pinfunction "1_1") (pintype "passive"))
      (node (ref "R4") (pin "2") (pinfunction "2_2") (pintype "passive"))
      (node (ref "R5") (pin "1") (pinfunction "1_1") (pintype "passive"))
      (node (ref "R6") (pin "2") (pinfunction "2_2") (pintype "passive"))
      (node (ref "R7") (pin "2") (pinfunction "2_2") (pintype "passive"))
      (node (ref "R8") (pin "2") (pinfunction "2_2") (pintype "passive"))
      (node (ref "R9") (pin "2") (pinfunction "2_2") (pintype "passive"))
      (node (ref "U1") (pin "16") (pinfunction "VDD2_16") (pintype "bidirectional"))
      (node (ref "U1") (pin "2") (pinfunction "VDD1_2") (pintype "bidirectional"))
      (node (ref "U1") (pin "30") (pinfunction "AVDD_30") (pintype "bidirectional"))
      (node (ref "U1") (pin "37") (pinfunction "VDD3_37") (pintype "bidirectional"))
      (node (ref "U1") (pin "46") (pinfunction "VDD4_46") (pintype "bidirectional"))
      (node (ref "U1") (pin "55") (pinfunction "VUSB_55") (pintype "bidirectional"))
      (node (ref "U1") (pin "62") (pinfunction "VDD5_62") (pintype "bidirectional"))
      (node (ref "U1") (pin "86") (pinfunction "ENVREG_86") (pintype "bidirectional"))
      (node (ref "U2") (pin "2") (pinfunction "OUT_2") (pintype "output"))
    )
    (net (code "88") (name "5V") (class "Default")
      (node (ref "5") (pin "1") (pinfunction "1_1") (pintype "passive"))
      (node (ref "C12") (pin "1") (pinfunction "1_1") (pintype "passive"))
      (node (ref "F1") (pin "2") (pinfunction "2_2") (pintype "passive"))
      (node (ref "J3") (pin "2") (pinfunction "2_2") (pintype "passive"))
      (node (ref "J4") (pin "39") (pinfunction "39_39") (pintype "passive"))
      (node (ref "U2") (pin "3") (pinfunction "IN_3") (pintype "input"))
    )
    (net (code "89") (name "GND") (class "Default")
      (node (ref "C1") (pin "C") (pinfunction "-_C") (pintype "passive"))
      (node (ref "C10") (pin "2") (pinfunction "2_2") (pintype "passive"))
      (node (ref "C11") (pin "2") (pinfunction "2_2") (pintype "passive"))
      (node (ref "C12") (pin "2") (pinfunction "2_2") (pintype "passive"))
      (node (ref "C13") (pin "2") (pinfunction "2_2") (pintype "passive"))
      (node (ref "C14") (pin "1") (pinfunction "1_1") (pintype "passive"))
      (node (ref "C15") (pin "1") (pinfunction "1_1") (pintype "passive"))
      (node (ref "C16") (pin "2") (pinfunction "2_2") (pintype "passive"))
      (node (ref "C17") (pin "2") (pinfunction "2_2") (pintype "passive"))
      (node (ref "C2") (pin "2") (pinfunction "2_2") (pintype "passive"))
      (node (ref "C3") (pin "2") (pinfunction "2_2") (pintype "passive"))
      (node (ref "C4") (pin "2") (pinfunction "2_2") (pintype "passive"))
      (node (ref "C5") (pin "C") (pinfunction "-_C") (pintype "passive"))
      (node (ref "C6") (pin "2") (pinfunction "2_2") (pintype "passive"))
      (node (ref "C7") (pin "2") (pinfunction "2_2") (pintype "passive"))
      (node (ref "C8") (pin "2") (pinfunction "2_2") (pintype "passive"))
      (node (ref "C9") (pin "2") (pinfunction "2_2") (pintype "passive"))
      (node (ref "J1") (pin "1") (pinfunction "1_1") (pintype "passive"))
      (node (ref "J2") (pin "1") (pinfunction "1_1") (pintype "passive"))
      (node (ref "J3") (pin "1") (pinfunction "1_1") (pintype "passive"))
      (node (ref "J4") (pin "40") (pinfunction "40_40") (pintype "passive"))
      (node (ref "J5") (pin "3") (pinfunction "3_3") (pintype "passive"))
      (node (ref "J6") (pin "5") (pinfunction "5_5") (pintype "passive"))
      (node (ref "J7") (pin "GND") (pinfunction "GND_GND") (pintype "bidirectional"))
      (node (ref "J8") (pin "G1") (pinfunction "P$1_G1") (pintype "bidirectional"))
      (node (ref "J8") (pin "G2") (pinfunction "P$2_G2") (pintype "bidirectional"))
      (node (ref "J8") (pin "G3") (pinfunction "P$3_G3") (pintype "bidirectional"))
      (node (ref "J8") (pin "G4") (pinfunction "SHIELD_G4") (pintype "bidirectional"))
      (node (ref "J8") (pin "GND") (pinfunction "GND_GND") (pintype "bidirectional"))
      (node (ref "PROGRAM") (pin "1") (pinfunction "1_1") (pintype "passive"))
      (node (ref "PROGRAM") (pin "2") (pinfunction "2_2") (pintype "passive"))
      (node (ref "PWR") (pin "C") (pinfunction "C_C") (pintype "passive"))
      (node (ref "R13") (pin "1") (pinfunction "1_1") (pintype "passive"))
      (node (ref "R15") (pin "1") (pinfunction "1_1") (pintype "passive"))
      (node (ref "RESET") (pin "1") (pinfunction "1_1") (pintype "passive"))
      (node (ref "RESET") (pin "2") (pinfunction "2_2") (pintype "passive"))
      (node (ref "U1") (pin "15") (pinfunction "VSS1_15") (pintype "bidirectional"))
      (node (ref "U1") (pin "31") (pinfunction "AVSS_31") (pintype "bidirectional"))
      (node (ref "U1") (pin "36") (pinfunction "VSS2_36") (pintype "bidirectional"))
      (node (ref "U1") (pin "45") (pinfunction "VSS3_45") (pintype "bidirectional"))
      (node (ref "U1") (pin "65") (pinfunction "VSS4_65") (pintype "bidirectional"))
      (node (ref "U1") (pin "75") (pinfunction "VSS6_75") (pintype "bidirectional"))
      (node (ref "USER") (pin "1") (pinfunction "1_1") (pintype "passive"))
      (node (ref "USER") (pin "2") (pinfunction "2_2") (pintype "passive"))
    )
    (net (code "90") (name "Net-(C1-+)") (class "Default")
      (node (ref "C1") (pin "A") (pinfunction "+_A") (pintype "passive"))
      (node (ref "D1") (pin "C") (pinfunction "C_C") (pintype "passive"))
      (node (ref "U3") (pin "3") (pinfunction "IN_3") (pintype "input"))
    )
    (net (code "91") (name "Net-(C5-+)") (class "Default")
      (node (ref "C4") (pin "1") (pinfunction "1_1") (pintype "passive"))
      (node (ref "C5") (pin "A") (pinfunction "+_A") (pintype "passive"))
      (node (ref "U1") (pin "85") (pinfunction "VCAP/VDDCORE_85") (pintype "bidirectional"))
    )
    (net (code "92") (name "Net-(D1-PadA)") (class "Default")
      (node (ref "D1") (pin "A") (pinfunction "A_A") (pintype "passive"))
      (node (ref "J1") (pin "2") (pinfunction "2_2") (pintype "passive"))
      (node (ref "J2") (pin "2") (pinfunction "2_2") (pintype "passive"))
    )
    (net (code "93") (name "Net-(F1-Pad1)") (class "Default")
      (node (ref "F1") (pin "1") (pinfunction "1_1") (pintype "passive"))
      (node (ref "PWR_SEL") (pin "2") (pinfunction "2_2") (pintype "bidirectional"))
      (node (ref "PWR_SEL") (pin "5") (pinfunction "5_5") (pintype "bidirectional"))
    )
    (net (code "94") (name "Net-(LED1-PadA)") (class "Default")
      (node (ref "LED1") (pin "A") (pinfunction "A_A") (pintype "passive"))
      (node (ref "R7") (pin "1") (pinfunction "1_1") (pintype "passive"))
    )
    (net (code "95") (name "Net-(LED2-PadA)") (class "Default")
      (node (ref "LED2") (pin "A") (pinfunction "A_A") (pintype "passive"))
      (node (ref "R6") (pin "1") (pinfunction "1_1") (pintype "passive"))
    )
    (net (code "96") (name "Net-(LED3-PadA)") (class "Default")
      (node (ref "LED3") (pin "A") (pinfunction "A_A") (pintype "passive"))
      (node (ref "R4") (pin "1") (pinfunction "1_1") (pintype "passive"))
    )
    (net (code "97") (name "Net-(PWR-PadA)") (class "Default")
      (node (ref "PWR") (pin "A") (pinfunction "A_A") (pintype "passive"))
      (node (ref "R11") (pin "1") (pinfunction "1_1") (pintype "passive"))
    )
    (net (code "98") (name "Net-(R8-Pad1)") (class "Default")
      (node (ref "R8") (pin "1") (pinfunction "1_1") (pintype "passive"))
      (node (ref "USB") (pin "A") (pinfunction "A_A") (pintype "passive"))
    )
    (net (code "99") (name "Net-(U2-ADJ)") (class "Default")
      (node (ref "R13") (pin "2") (pinfunction "2_2") (pintype "passive"))
      (node (ref "R14") (pin "2") (pinfunction "2_2") (pintype "passive"))
      (node (ref "U2") (pin "1") (pinfunction "ADJ_1") (pintype "input"))
    )
    (net (code "100") (name "Net-(U3-ADJ)") (class "Default")
      (node (ref "R15") (pin "2") (pinfunction "2_2") (pintype "passive"))
      (node (ref "R16") (pin "2") (pinfunction "2_2") (pintype "passive"))
      (node (ref "U3") (pin "1") (pinfunction "ADJ_1") (pintype "input"))
    )
  )
)
